# Connectors.net
KiCad netlist of a schematic drawn in Altium Designer
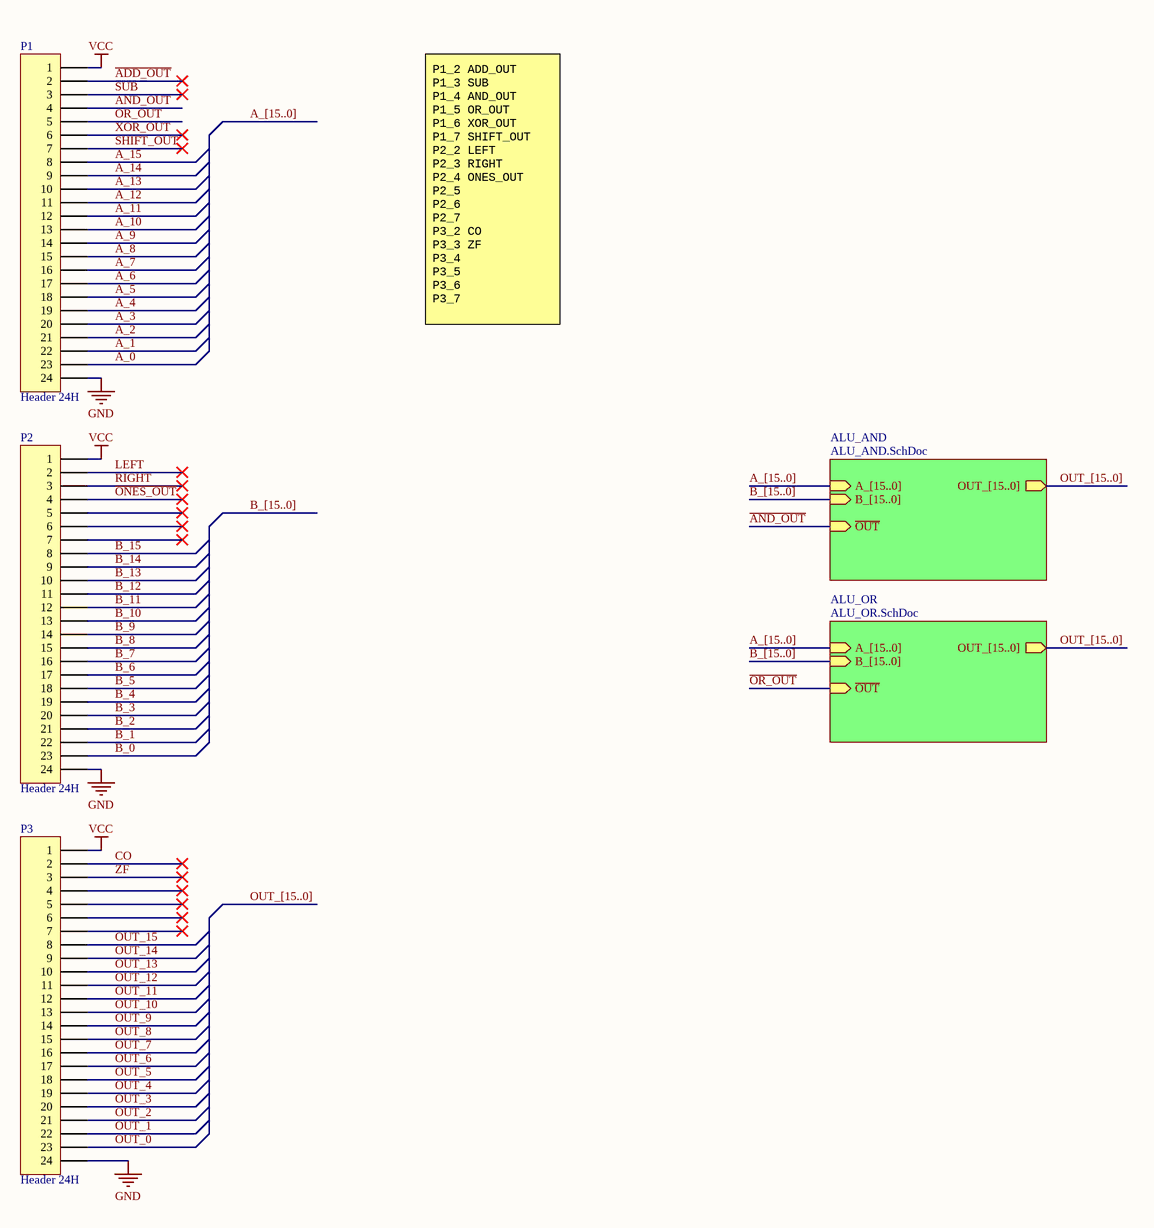
[diagram p0: Connectors.SchDoc]

(export (version "E")
  (design (tool "Eeschema 10.0.6"))
  (components
    (comp (ref "P1")
      (value "Header 24H")
      (footprint "HDR1X24H")
      (description "Header, 24-Pin, Right Angle")
      (fields (field (name "PUBLISHER") "Altium Limited"))
      (libsource (lib "Miscellaneous Connectors") (part "Header 24H"))
    )
    (comp (ref "P2")
      (value "Header 24H")
      (footprint "HDR1X24H")
      (description "Header, 24-Pin, Right Angle")
      (fields (field (name "PUBLISHER") "Altium Limited"))
      (libsource (lib "Miscellaneous Connectors") (part "Header 24H"))
    )
    (comp (ref "P3")
      (value "Header 24H")
      (footprint "HDR1X24H")
      (description "Header, 24-Pin, Right Angle")
      (fields (field (name "PUBLISHER") "Altium Limited"))
      (libsource (lib "Miscellaneous Connectors") (part "Header 24H"))
    )
  )
  (nets
    (net (code "1") (name "/A_0") (class "Default")
      (node (ref "P1") (pin "23") (pinfunction "23_23") (pintype "passive"))
    )
    (net (code "2") (name "/A_1") (class "Default")
      (node (ref "P1") (pin "22") (pinfunction "22_22") (pintype "passive"))
    )
    (net (code "3") (name "/A_2") (class "Default")
      (node (ref "P1") (pin "21") (pinfunction "21_21") (pintype "passive"))
    )
    (net (code "4") (name "/A_3") (class "Default")
      (node (ref "P1") (pin "20") (pinfunction "20_20") (pintype "passive"))
    )
    (net (code "5") (name "/A_4") (class "Default")
      (node (ref "P1") (pin "19") (pinfunction "19_19") (pintype "passive"))
    )
    (net (code "6") (name "/A_5") (class "Default")
      (node (ref "P1") (pin "18") (pinfunction "18_18") (pintype "passive"))
    )
    (net (code "7") (name "/A_6") (class "Default")
      (node (ref "P1") (pin "17") (pinfunction "17_17") (pintype "passive"))
    )
    (net (code "8") (name "/A_7") (class "Default")
      (node (ref "P1") (pin "16") (pinfunction "16_16") (pintype "passive"))
    )
    (net (code "9") (name "/A_8") (class "Default")
      (node (ref "P1") (pin "15") (pinfunction "15_15") (pintype "passive"))
    )
    (net (code "10") (name "/A_9") (class "Default")
      (node (ref "P1") (pin "14") (pinfunction "14_14") (pintype "passive"))
    )
    (net (code "11") (name "/A_10") (class "Default")
      (node (ref "P1") (pin "13") (pinfunction "13_13") (pintype "passive"))
    )
    (net (code "12") (name "/A_11") (class "Default")
      (node (ref "P1") (pin "12") (pinfunction "12_12") (pintype "passive"))
    )
    (net (code "13") (name "/A_12") (class "Default")
      (node (ref "P1") (pin "11") (pinfunction "11_11") (pintype "passive"))
    )
    (net (code "14") (name "/A_13") (class "Default")
      (node (ref "P1") (pin "10") (pinfunction "10_10") (pintype "passive"))
    )
    (net (code "15") (name "/A_14") (class "Default")
      (node (ref "P1") (pin "9") (pinfunction "9_9") (pintype "passive"))
    )
    (net (code "16") (name "/A_15") (class "Default")
      (node (ref "P1") (pin "8") (pinfunction "8_8") (pintype "passive"))
    )
    (net (code "18") (name "/B_0") (class "Default")
      (node (ref "P2") (pin "23") (pinfunction "23_23") (pintype "passive"))
    )
    (net (code "19") (name "/B_1") (class "Default")
      (node (ref "P2") (pin "22") (pinfunction "22_22") (pintype "passive"))
    )
    (net (code "20") (name "/B_2") (class "Default")
      (node (ref "P2") (pin "21") (pinfunction "21_21") (pintype "passive"))
    )
    (net (code "21") (name "/B_3") (class "Default")
      (node (ref "P2") (pin "20") (pinfunction "20_20") (pintype "passive"))
    )
    (net (code "22") (name "/B_4") (class "Default")
      (node (ref "P2") (pin "19") (pinfunction "19_19") (pintype "passive"))
    )
    (net (code "23") (name "/B_5") (class "Default")
      (node (ref "P2") (pin "18") (pinfunction "18_18") (pintype "passive"))
    )
    (net (code "24") (name "/B_6") (class "Default")
      (node (ref "P2") (pin "17") (pinfunction "17_17") (pintype "passive"))
    )
    (net (code "25") (name "/B_7") (class "Default")
      (node (ref "P2") (pin "16") (pinfunction "16_16") (pintype "passive"))
    )
    (net (code "26") (name "/B_8") (class "Default")
      (node (ref "P2") (pin "15") (pinfunction "15_15") (pintype "passive"))
    )
    (net (code "27") (name "/B_9") (class "Default")
      (node (ref "P2") (pin "14") (pinfunction "14_14") (pintype "passive"))
    )
    (net (code "28") (name "/B_10") (class "Default")
      (node (ref "P2") (pin "13") (pinfunction "13_13") (pintype "passive"))
    )
    (net (code "29") (name "/B_11") (class "Default")
      (node (ref "P2") (pin "12") (pinfunction "12_12") (pintype "passive"))
    )
    (net (code "30") (name "/B_12") (class "Default")
      (node (ref "P2") (pin "11") (pinfunction "11_11") (pintype "passive"))
    )
    (net (code "31") (name "/B_13") (class "Default")
      (node (ref "P2") (pin "10") (pinfunction "10_10") (pintype "passive"))
    )
    (net (code "32") (name "/B_14") (class "Default")
      (node (ref "P2") (pin "9") (pinfunction "9_9") (pintype "passive"))
    )
    (net (code "33") (name "/B_15") (class "Default")
      (node (ref "P2") (pin "8") (pinfunction "8_8") (pintype "passive"))
    )
    (net (code "35") (name "/CO") (class "Default")
      (node (ref "P3") (pin "2") (pinfunction "2_2") (pintype "passive+no_connect"))
    )
    (net (code "36") (name "/LEFT") (class "Default")
      (node (ref "P2") (pin "2") (pinfunction "2_2") (pintype "passive+no_connect"))
    )
    (net (code "37") (name "/OUT_0") (class "Default")
      (node (ref "P3") (pin "23") (pinfunction "23_23") (pintype "passive"))
    )
    (net (code "38") (name "/OUT_1") (class "Default")
      (node (ref "P3") (pin "22") (pinfunction "22_22") (pintype "passive"))
    )
    (net (code "39") (name "/OUT_2") (class "Default")
      (node (ref "P3") (pin "21") (pinfunction "21_21") (pintype "passive"))
    )
    (net (code "40") (name "/OUT_3") (class "Default")
      (node (ref "P3") (pin "20") (pinfunction "20_20") (pintype "passive"))
    )
    (net (code "41") (name "/OUT_4") (class "Default")
      (node (ref "P3") (pin "19") (pinfunction "19_19") (pintype "passive"))
    )
    (net (code "42") (name "/OUT_5") (class "Default")
      (node (ref "P3") (pin "18") (pinfunction "18_18") (pintype "passive"))
    )
    (net (code "43") (name "/OUT_6") (class "Default")
      (node (ref "P3") (pin "17") (pinfunction "17_17") (pintype "passive"))
    )
    (net (code "44") (name "/OUT_7") (class "Default")
      (node (ref "P3") (pin "16") (pinfunction "16_16") (pintype "passive"))
    )
    (net (code "45") (name "/OUT_8") (class "Default")
      (node (ref "P3") (pin "15") (pinfunction "15_15") (pintype "passive"))
    )
    (net (code "46") (name "/OUT_9") (class "Default")
      (node (ref "P3") (pin "14") (pinfunction "14_14") (pintype "passive"))
    )
    (net (code "47") (name "/OUT_10") (class "Default")
      (node (ref "P3") (pin "13") (pinfunction "13_13") (pintype "passive"))
    )
    (net (code "48") (name "/OUT_11") (class "Default")
      (node (ref "P3") (pin "12") (pinfunction "12_12") (pintype "passive"))
    )
    (net (code "49") (name "/OUT_12") (class "Default")
      (node (ref "P3") (pin "11") (pinfunction "11_11") (pintype "passive"))
    )
    (net (code "50") (name "/OUT_13") (class "Default")
      (node (ref "P3") (pin "10") (pinfunction "10_10") (pintype "passive"))
    )
    (net (code "51") (name "/OUT_14") (class "Default")
      (node (ref "P3") (pin "9") (pinfunction "9_9") (pintype "passive"))
    )
    (net (code "52") (name "/OUT_15") (class "Default")
      (node (ref "P3") (pin "8") (pinfunction "8_8") (pintype "passive"))
    )
    (net (code "54") (name "/RIGHT") (class "Default")
      (node (ref "P2") (pin "3") (pinfunction "3_3") (pintype "passive+no_connect"))
    )
    (net (code "55") (name "/SUB") (class "Default")
      (node (ref "P1") (pin "3") (pinfunction "3_3") (pintype "passive+no_connect"))
    )
    (net (code "56") (name "/~{ADD_OUT}") (class "Default")
      (node (ref "P1") (pin "2") (pinfunction "2_2") (pintype "passive+no_connect"))
    )
    (net (code "57") (name "/~{AND_OUT}") (class "Default")
      (node (ref "P1") (pin "4") (pinfunction "4_4") (pintype "passive"))
    )
    (net (code "58") (name "/~{ONES_OUT}") (class "Default")
      (node (ref "P2") (pin "4") (pinfunction "4_4") (pintype "passive+no_connect"))
    )
    (net (code "59") (name "/~{OR_OUT}") (class "Default")
      (node (ref "P1") (pin "5") (pinfunction "5_5") (pintype "passive"))
    )
    (net (code "60") (name "/~{SHIFT_OUT}") (class "Default")
      (node (ref "P1") (pin "7") (pinfunction "7_7") (pintype "passive+no_connect"))
    )
    (net (code "61") (name "/~{XOR_OUT}") (class "Default")
      (node (ref "P1") (pin "6") (pinfunction "6_6") (pintype "passive+no_connect"))
    )
    (net (code "62") (name "/~{ZF}") (class "Default")
      (node (ref "P3") (pin "3") (pinfunction "3_3") (pintype "passive+no_connect"))
    )
    (net (code "63") (name "GND") (class "Default")
      (node (ref "P1") (pin "24") (pinfunction "24_24") (pintype "passive"))
      (node (ref "P2") (pin "24") (pinfunction "24_24") (pintype "passive"))
      (node (ref "P3") (pin "24") (pinfunction "24_24") (pintype "passive"))
    )
    (net (code "64") (name "VCC") (class "Default")
      (node (ref "P1") (pin "1") (pinfunction "1_1") (pintype "passive"))
      (node (ref "P2") (pin "1") (pinfunction "1_1") (pintype "passive"))
      (node (ref "P3") (pin "1") (pinfunction "1_1") (pintype "passive"))
    )
    (net (code "65") (name "unconnected-(P2-Pad5)") (class "Default")
      (node (ref "P2") (pin "5") (pinfunction "5_5") (pintype "passive+no_connect"))
    )
    (net (code "66") (name "unconnected-(P2-Pad6)") (class "Default")
      (node (ref "P2") (pin "6") (pinfunction "6_6") (pintype "passive+no_connect"))
    )
    (net (code "67") (name "unconnected-(P2-Pad7)") (class "Default")
      (node (ref "P2") (pin "7") (pinfunction "7_7") (pintype "passive+no_connect"))
    )
    (net (code "68") (name "unconnected-(P3-Pad4)") (class "Default")
      (node (ref "P3") (pin "4") (pinfunction "4_4") (pintype "passive+no_connect"))
    )
    (net (code "69") (name "unconnected-(P3-Pad5)") (class "Default")
      (node (ref "P3") (pin "5") (pinfunction "5_5") (pintype "passive+no_connect"))
    )
    (net (code "70") (name "unconnected-(P3-Pad6)") (class "Default")
      (node (ref "P3") (pin "6") (pinfunction "6_6") (pintype "passive+no_connect"))
    )
    (net (code "71") (name "unconnected-(P3-Pad7)") (class "Default")
      (node (ref "P3") (pin "7") (pinfunction "7_7") (pintype "passive+no_connect"))
    )
  )
)
